# plate_template.net
KiCad netlist of a schematic drawn in EAGLE
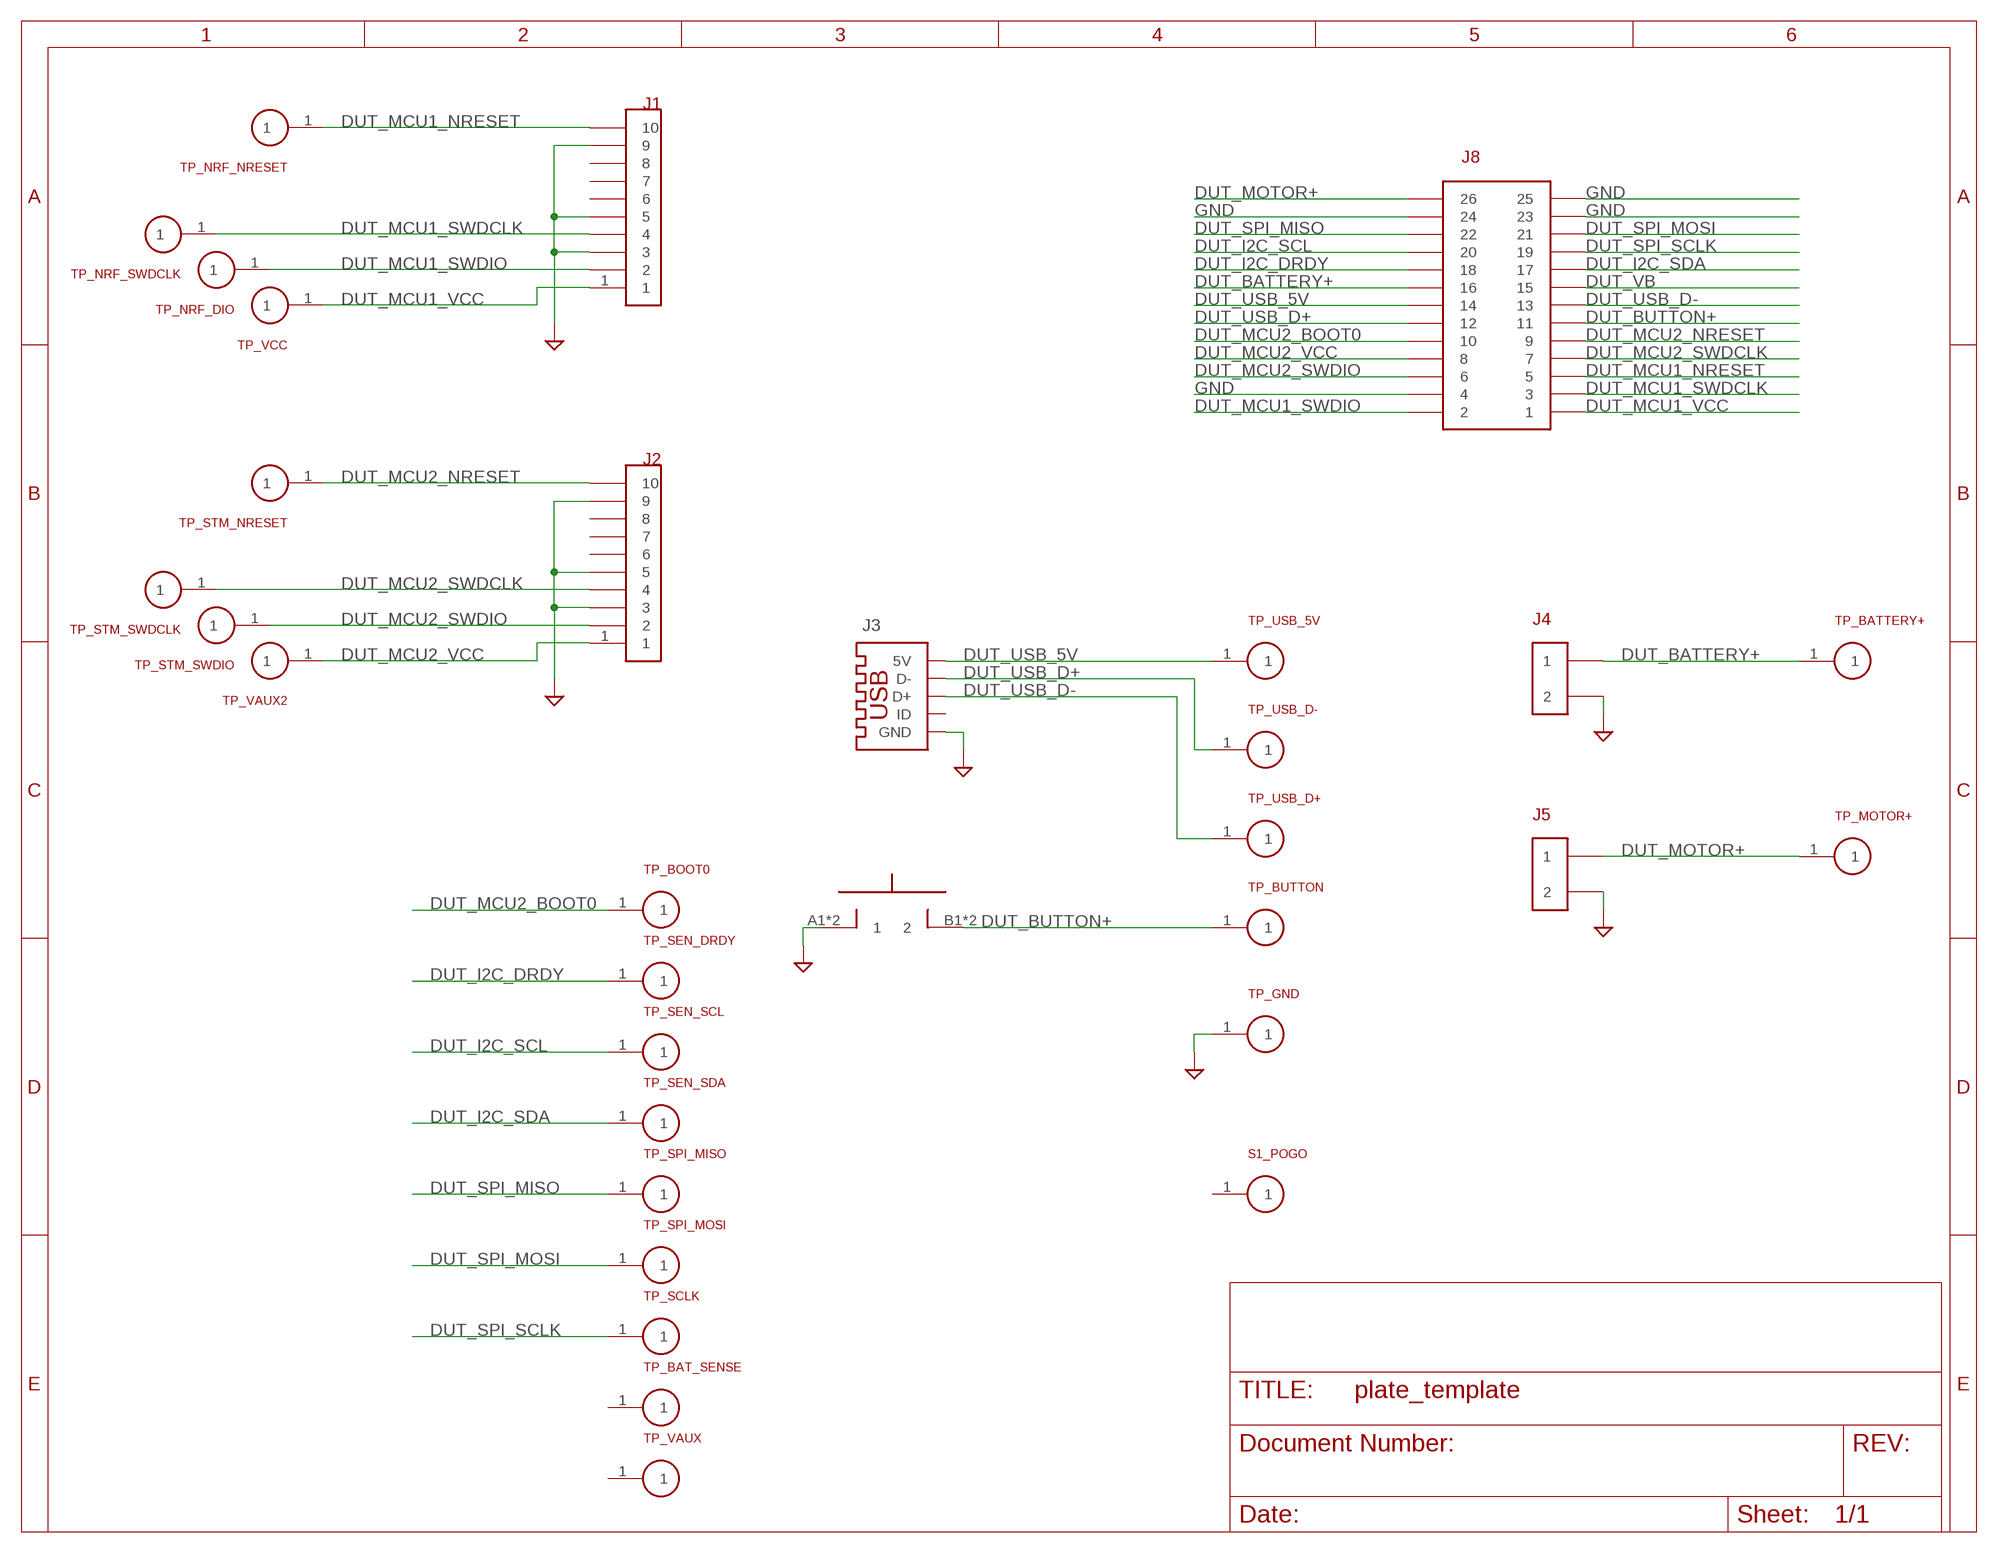
[diagram p0: schematic, sheet 1]

(export (version "E")
  (design (tool "Eeschema 10.0.6"))
  (components
    (comp (ref "J1")
      (value "CON-10SWD")
      (footprint "eagle-import:SWD-10")
      (libsource (lib "eagle-import") (part "CON-10SWD"))
    )
    (comp (ref "J2")
      (value "CON-10SWD")
      (footprint "eagle-import:SWD-10")
      (libsource (lib "eagle-import") (part "CON-10SWD"))
    )
    (comp (ref "J3")
      (value "USB-5PIN10118193")
      (footprint "eagle-import:10118193")
      (fields (field (name "MANUFACTURER") "Amphenol FCI"))
      (libsource (lib "eagle-import") (part "USB-5PIN10118193"))
    )
    (comp (ref "J4")
      (value "CON-2CON-HEADER-2")
      (footprint "eagle-import:CON-HEADER-2")
      (fields (field (name "MANUFACTURER") "FCI"))
      (libsource (lib "eagle-import") (part "CON-2CON-HEADER-2"))
    )
    (comp (ref "J5")
      (value "CON-2CON-HEADER-2")
      (footprint "eagle-import:CON-HEADER-2")
      (fields (field (name "MANUFACTURER") "FCI"))
      (libsource (lib "eagle-import") (part "CON-2CON-HEADER-2"))
    )
    (comp (ref "J8")
      (value "CON-26")
      (footprint "eagle-import:CON-HEADER-2X13")
      (fields (field (name "MANUFACTURER") "Amphenol FCI"))
      (libsource (lib "eagle-import") (part "CON-26"))
    )
    (comp (ref "S1")
      (value "SPST-NORACON8")
      (footprint "eagle-import:RACON8")
      (fields (field (name "MANUFACTURER") "RAFI USA"))
      (libsource (lib "eagle-import") (part "SPST-NORACON8"))
    )
    (comp (ref "S1_POGO")
      (value "TARGET-PINPROBE-0985")
      (footprint "eagle-import:PROBE-0985")
      (libsource (lib "eagle-import") (part "TARGET-PINPROBE-0985"))
    )
    (comp (ref "TP_BATTERY+")
      (value "TARGET-PINPROBE-0985")
      (footprint "eagle-import:PROBE-0985")
      (libsource (lib "eagle-import") (part "TARGET-PINPROBE-0985"))
    )
    (comp (ref "TP_BAT_SENSE")
      (value "TARGET-PINPROBE-0985")
      (footprint "eagle-import:PROBE-0985")
      (libsource (lib "eagle-import") (part "TARGET-PINPROBE-0985"))
    )
    (comp (ref "TP_BOOT0")
      (value "TARGET-PINPROBE-0985")
      (footprint "eagle-import:PROBE-0985")
      (libsource (lib "eagle-import") (part "TARGET-PINPROBE-0985"))
    )
    (comp (ref "TP_BUTTON")
      (value "TARGET-PINPROBE-0985")
      (footprint "eagle-import:PROBE-0985")
      (libsource (lib "eagle-import") (part "TARGET-PINPROBE-0985"))
    )
    (comp (ref "TP_GND")
      (value "TARGET-PINPROBE-0985")
      (footprint "eagle-import:PROBE-0985")
      (libsource (lib "eagle-import") (part "TARGET-PINPROBE-0985"))
    )
    (comp (ref "TP_MOTOR+")
      (value "TARGET-PINPROBE-0985")
      (footprint "eagle-import:PROBE-0985")
      (libsource (lib "eagle-import") (part "TARGET-PINPROBE-0985"))
    )
    (comp (ref "TP_NRF_DIO")
      (value "TARGET-PINPROBE-0985")
      (footprint "eagle-import:PROBE-0985")
      (libsource (lib "eagle-import") (part "TARGET-PINPROBE-0985"))
    )
    (comp (ref "TP_NRF_NRESET")
      (value "TARGET-PINPROBE-0985")
      (footprint "eagle-import:PROBE-0985")
      (libsource (lib "eagle-import") (part "TARGET-PINPROBE-0985"))
    )
    (comp (ref "TP_NRF_SWDCLK")
      (value "TARGET-PINPROBE-0985")
      (footprint "eagle-import:PROBE-0985")
      (libsource (lib "eagle-import") (part "TARGET-PINPROBE-0985"))
    )
    (comp (ref "TP_SCLK")
      (value "TARGET-PINPROBE-0985")
      (footprint "eagle-import:PROBE-0985")
      (libsource (lib "eagle-import") (part "TARGET-PINPROBE-0985"))
    )
    (comp (ref "TP_SEN_DRDY")
      (value "TARGET-PINPROBE-0985")
      (footprint "eagle-import:PROBE-0985")
      (libsource (lib "eagle-import") (part "TARGET-PINPROBE-0985"))
    )
    (comp (ref "TP_SEN_SCL")
      (value "TARGET-PINPROBE-0985")
      (footprint "eagle-import:PROBE-0985")
      (libsource (lib "eagle-import") (part "TARGET-PINPROBE-0985"))
    )
    (comp (ref "TP_SEN_SDA")
      (value "TARGET-PINPROBE-0985")
      (footprint "eagle-import:PROBE-0985")
      (libsource (lib "eagle-import") (part "TARGET-PINPROBE-0985"))
    )
    (comp (ref "TP_SPI_MISO")
      (value "TARGET-PINPROBE-0985")
      (footprint "eagle-import:PROBE-0985")
      (libsource (lib "eagle-import") (part "TARGET-PINPROBE-0985"))
    )
    (comp (ref "TP_SPI_MOSI")
      (value "TARGET-PINPROBE-0985")
      (footprint "eagle-import:PROBE-0985")
      (libsource (lib "eagle-import") (part "TARGET-PINPROBE-0985"))
    )
    (comp (ref "TP_STM_NRESET")
      (value "TARGET-PINPROBE-0985")
      (footprint "eagle-import:PROBE-0985")
      (libsource (lib "eagle-import") (part "TARGET-PINPROBE-0985"))
    )
    (comp (ref "TP_STM_SWDCLK")
      (value "TARGET-PINPROBE-0985")
      (footprint "eagle-import:PROBE-0985")
      (libsource (lib "eagle-import") (part "TARGET-PINPROBE-0985"))
    )
    (comp (ref "TP_STM_SWDIO")
      (value "TARGET-PINPROBE-0985")
      (footprint "eagle-import:PROBE-0985")
      (libsource (lib "eagle-import") (part "TARGET-PINPROBE-0985"))
    )
    (comp (ref "TP_USB_5V")
      (value "TARGET-PINPROBE-0985")
      (footprint "eagle-import:PROBE-0985")
      (libsource (lib "eagle-import") (part "TARGET-PINPROBE-0985"))
    )
    (comp (ref "TP_USB_D+")
      (value "TARGET-PINPROBE-0985")
      (footprint "eagle-import:PROBE-0985")
      (libsource (lib "eagle-import") (part "TARGET-PINPROBE-0985"))
    )
    (comp (ref "TP_USB_D-")
      (value "TARGET-PINPROBE-0985")
      (footprint "eagle-import:PROBE-0985")
      (libsource (lib "eagle-import") (part "TARGET-PINPROBE-0985"))
    )
    (comp (ref "TP_VAUX")
      (value "TARGET-PINPROBE-0985")
      (footprint "eagle-import:PROBE-0985")
      (libsource (lib "eagle-import") (part "TARGET-PINPROBE-0985"))
    )
    (comp (ref "TP_VAUX2")
      (value "TARGET-PINPROBE-0985")
      (footprint "eagle-import:PROBE-0985")
      (libsource (lib "eagle-import") (part "TARGET-PINPROBE-0985"))
    )
    (comp (ref "TP_VCC")
      (value "TARGET-PINPROBE-0985")
      (footprint "eagle-import:PROBE-0985")
      (libsource (lib "eagle-import") (part "TARGET-PINPROBE-0985"))
    )
  )
  (nets
    (net (code "1") (name "/DUT_BATTERY+") (class "Default")
      (node (ref "J4") (pin "1") (pinfunction "1_1") (pintype "bidirectional"))
      (node (ref "J8") (pin "16") (pinfunction "16_16") (pintype "bidirectional"))
      (node (ref "TP_BATTERY+") (pin "1") (pinfunction "1_1") (pintype "bidirectional"))
    )
    (net (code "2") (name "/DUT_BUTTON+") (class "Default")
      (node (ref "J8") (pin "11") (pinfunction "11_11") (pintype "bidirectional"))
      (node (ref "S1") (pin "B1") (pinfunction "2_B1") (pintype "bidirectional"))
      (node (ref "S1") (pin "B2") (pinfunction "2_B2") (pintype "bidirectional"))
      (node (ref "TP_BUTTON") (pin "1") (pinfunction "1_1") (pintype "bidirectional"))
    )
    (net (code "3") (name "/DUT_I2C_DRDY") (class "Default")
      (node (ref "J8") (pin "18") (pinfunction "18_18") (pintype "bidirectional"))
      (node (ref "TP_SEN_DRDY") (pin "1") (pinfunction "1_1") (pintype "bidirectional"))
    )
    (net (code "4") (name "/DUT_I2C_SCL") (class "Default")
      (node (ref "J8") (pin "20") (pinfunction "20_20") (pintype "bidirectional"))
      (node (ref "TP_SEN_SCL") (pin "1") (pinfunction "1_1") (pintype "bidirectional"))
    )
    (net (code "5") (name "/DUT_I2C_SDA") (class "Default")
      (node (ref "J8") (pin "17") (pinfunction "17_17") (pintype "bidirectional"))
      (node (ref "TP_SEN_SDA") (pin "1") (pinfunction "1_1") (pintype "bidirectional"))
    )
    (net (code "6") (name "/DUT_MCU1_NRESET") (class "Default")
      (node (ref "J1") (pin "10") (pinfunction "10_10") (pintype "bidirectional"))
      (node (ref "J8") (pin "5") (pinfunction "5_5") (pintype "bidirectional"))
      (node (ref "TP_NRF_NRESET") (pin "1") (pinfunction "1_1") (pintype "bidirectional"))
    )
    (net (code "7") (name "/DUT_MCU1_SWDCLK") (class "Default")
      (node (ref "J1") (pin "4") (pinfunction "4_4") (pintype "bidirectional"))
      (node (ref "J8") (pin "3") (pinfunction "3_3") (pintype "bidirectional"))
      (node (ref "TP_NRF_SWDCLK") (pin "1") (pinfunction "1_1") (pintype "bidirectional"))
    )
    (net (code "8") (name "/DUT_MCU1_SWDIO") (class "Default")
      (node (ref "J1") (pin "2") (pinfunction "2_2") (pintype "bidirectional"))
      (node (ref "J8") (pin "2") (pinfunction "2_2") (pintype "bidirectional"))
      (node (ref "TP_NRF_DIO") (pin "1") (pinfunction "1_1") (pintype "bidirectional"))
    )
    (net (code "9") (name "/DUT_MCU1_VCC") (class "Default")
      (node (ref "J1") (pin "1") (pinfunction "1_1") (pintype "bidirectional"))
      (node (ref "J8") (pin "1") (pinfunction "1_1") (pintype "bidirectional"))
      (node (ref "TP_VCC") (pin "1") (pinfunction "1_1") (pintype "bidirectional"))
    )
    (net (code "10") (name "/DUT_MCU2_BOOT0") (class "Default")
      (node (ref "J8") (pin "10") (pinfunction "10_10") (pintype "bidirectional"))
      (node (ref "TP_BOOT0") (pin "1") (pinfunction "1_1") (pintype "bidirectional"))
    )
    (net (code "11") (name "/DUT_MCU2_NRESET") (class "Default")
      (node (ref "J2") (pin "10") (pinfunction "10_10") (pintype "bidirectional"))
      (node (ref "J8") (pin "9") (pinfunction "9_9") (pintype "bidirectional"))
      (node (ref "TP_STM_NRESET") (pin "1") (pinfunction "1_1") (pintype "bidirectional"))
    )
    (net (code "12") (name "/DUT_MCU2_SWDCLK") (class "Default")
      (node (ref "J2") (pin "4") (pinfunction "4_4") (pintype "bidirectional"))
      (node (ref "J8") (pin "7") (pinfunction "7_7") (pintype "bidirectional"))
      (node (ref "TP_STM_SWDCLK") (pin "1") (pinfunction "1_1") (pintype "bidirectional"))
    )
    (net (code "13") (name "/DUT_MCU2_SWDIO") (class "Default")
      (node (ref "J2") (pin "2") (pinfunction "2_2") (pintype "bidirectional"))
      (node (ref "J8") (pin "6") (pinfunction "6_6") (pintype "bidirectional"))
      (node (ref "TP_STM_SWDIO") (pin "1") (pinfunction "1_1") (pintype "bidirectional"))
    )
    (net (code "14") (name "/DUT_MCU2_VCC") (class "Default")
      (node (ref "J2") (pin "1") (pinfunction "1_1") (pintype "bidirectional"))
      (node (ref "J8") (pin "8") (pinfunction "8_8") (pintype "bidirectional"))
      (node (ref "TP_VAUX2") (pin "1") (pinfunction "1_1") (pintype "bidirectional"))
    )
    (net (code "15") (name "/DUT_MOTOR+") (class "Default")
      (node (ref "J5") (pin "1") (pinfunction "1_1") (pintype "bidirectional"))
      (node (ref "J8") (pin "26") (pinfunction "26_26") (pintype "bidirectional"))
      (node (ref "TP_MOTOR+") (pin "1") (pinfunction "1_1") (pintype "bidirectional"))
    )
    (net (code "16") (name "/DUT_SPI_MISO") (class "Default")
      (node (ref "J8") (pin "22") (pinfunction "22_22") (pintype "bidirectional"))
      (node (ref "TP_SPI_MISO") (pin "1") (pinfunction "1_1") (pintype "bidirectional"))
    )
    (net (code "17") (name "/DUT_SPI_MOSI") (class "Default")
      (node (ref "J8") (pin "21") (pinfunction "21_21") (pintype "bidirectional"))
      (node (ref "TP_SPI_MOSI") (pin "1") (pinfunction "1_1") (pintype "bidirectional"))
    )
    (net (code "18") (name "/DUT_SPI_SCLK") (class "Default")
      (node (ref "J8") (pin "19") (pinfunction "19_19") (pintype "bidirectional"))
      (node (ref "TP_SCLK") (pin "1") (pinfunction "1_1") (pintype "bidirectional"))
    )
    (net (code "19") (name "/DUT_USB_5V") (class "Default")
      (node (ref "J3") (pin "1") (pinfunction "5V_1") (pintype "bidirectional"))
      (node (ref "J8") (pin "14") (pinfunction "14_14") (pintype "bidirectional"))
      (node (ref "TP_USB_5V") (pin "1") (pinfunction "1_1") (pintype "bidirectional"))
    )
    (net (code "20") (name "/DUT_USB_D+") (class "Default")
      (node (ref "J3") (pin "2") (pinfunction "D-_2") (pintype "bidirectional"))
      (node (ref "J8") (pin "12") (pinfunction "12_12") (pintype "bidirectional"))
      (node (ref "TP_USB_D-") (pin "1") (pinfunction "1_1") (pintype "bidirectional"))
    )
    (net (code "21") (name "/DUT_USB_D-") (class "Default")
      (node (ref "J3") (pin "3") (pinfunction "D+_3") (pintype "bidirectional"))
      (node (ref "J8") (pin "13") (pinfunction "13_13") (pintype "bidirectional"))
      (node (ref "TP_USB_D+") (pin "1") (pinfunction "1_1") (pintype "bidirectional"))
    )
    (net (code "22") (name "/DUT_VB") (class "Default")
      (node (ref "J8") (pin "15") (pinfunction "15_15") (pintype "bidirectional"))
    )
    (net (code "23") (name "GND") (class "Default")
      (node (ref "J1") (pin "3") (pinfunction "3_3") (pintype "bidirectional"))
      (node (ref "J1") (pin "5") (pinfunction "5_5") (pintype "bidirectional"))
      (node (ref "J1") (pin "9") (pinfunction "9_9") (pintype "bidirectional"))
      (node (ref "J2") (pin "3") (pinfunction "3_3") (pintype "bidirectional"))
      (node (ref "J2") (pin "5") (pinfunction "5_5") (pintype "bidirectional"))
      (node (ref "J2") (pin "9") (pinfunction "9_9") (pintype "bidirectional"))
      (node (ref "J3") (pin "5") (pinfunction "GND_5") (pintype "bidirectional"))
      (node (ref "J4") (pin "2") (pinfunction "2_2") (pintype "bidirectional"))
      (node (ref "J5") (pin "2") (pinfunction "2_2") (pintype "bidirectional"))
      (node (ref "J8") (pin "23") (pinfunction "23_23") (pintype "bidirectional"))
      (node (ref "J8") (pin "24") (pinfunction "24_24") (pintype "bidirectional"))
      (node (ref "J8") (pin "25") (pinfunction "25_25") (pintype "bidirectional"))
      (node (ref "J8") (pin "4") (pinfunction "4_4") (pintype "bidirectional"))
      (node (ref "S1") (pin "A1") (pinfunction "1_A1") (pintype "bidirectional"))
      (node (ref "S1") (pin "A2") (pinfunction "1_A2") (pintype "bidirectional"))
      (node (ref "TP_GND") (pin "1") (pinfunction "1_1") (pintype "bidirectional"))
    )
    (net (code "24") (name "unconnected-(J1-Pad6)") (class "Default")
      (node (ref "J1") (pin "6") (pinfunction "6_6") (pintype "bidirectional"))
    )
    (net (code "25") (name "unconnected-(J1-Pad7)") (class "Default")
      (node (ref "J1") (pin "7") (pinfunction "7_7") (pintype "bidirectional"))
    )
    (net (code "26") (name "unconnected-(J1-Pad8)") (class "Default")
      (node (ref "J1") (pin "8") (pinfunction "8_8") (pintype "bidirectional"))
    )
    (net (code "27") (name "unconnected-(J2-Pad6)") (class "Default")
      (node (ref "J2") (pin "6") (pinfunction "6_6") (pintype "bidirectional"))
    )
    (net (code "28") (name "unconnected-(J2-Pad7)") (class "Default")
      (node (ref "J2") (pin "7") (pinfunction "7_7") (pintype "bidirectional"))
    )
    (net (code "29") (name "unconnected-(J2-Pad8)") (class "Default")
      (node (ref "J2") (pin "8") (pinfunction "8_8") (pintype "bidirectional"))
    )
    (net (code "30") (name "unconnected-(J3-ID-Pad4)") (class "Default")
      (node (ref "J3") (pin "4") (pinfunction "ID_4") (pintype "bidirectional"))
    )
    (net (code "31") (name "unconnected-(S1_POGO-Pad1)") (class "Default")
      (node (ref "S1_POGO") (pin "1") (pinfunction "1_1") (pintype "bidirectional"))
    )
    (net (code "32") (name "unconnected-(TP_BAT_SENSE-Pad1)") (class "Default")
      (node (ref "TP_BAT_SENSE") (pin "1") (pinfunction "1_1") (pintype "bidirectional"))
    )
    (net (code "33") (name "unconnected-(TP_VAUX-Pad1)") (class "Default")
      (node (ref "TP_VAUX") (pin "1") (pinfunction "1_1") (pintype "bidirectional"))
    )
  )
)
